# raspi_mockup.net
KiCad netlist of a schematic drawn in EAGLE
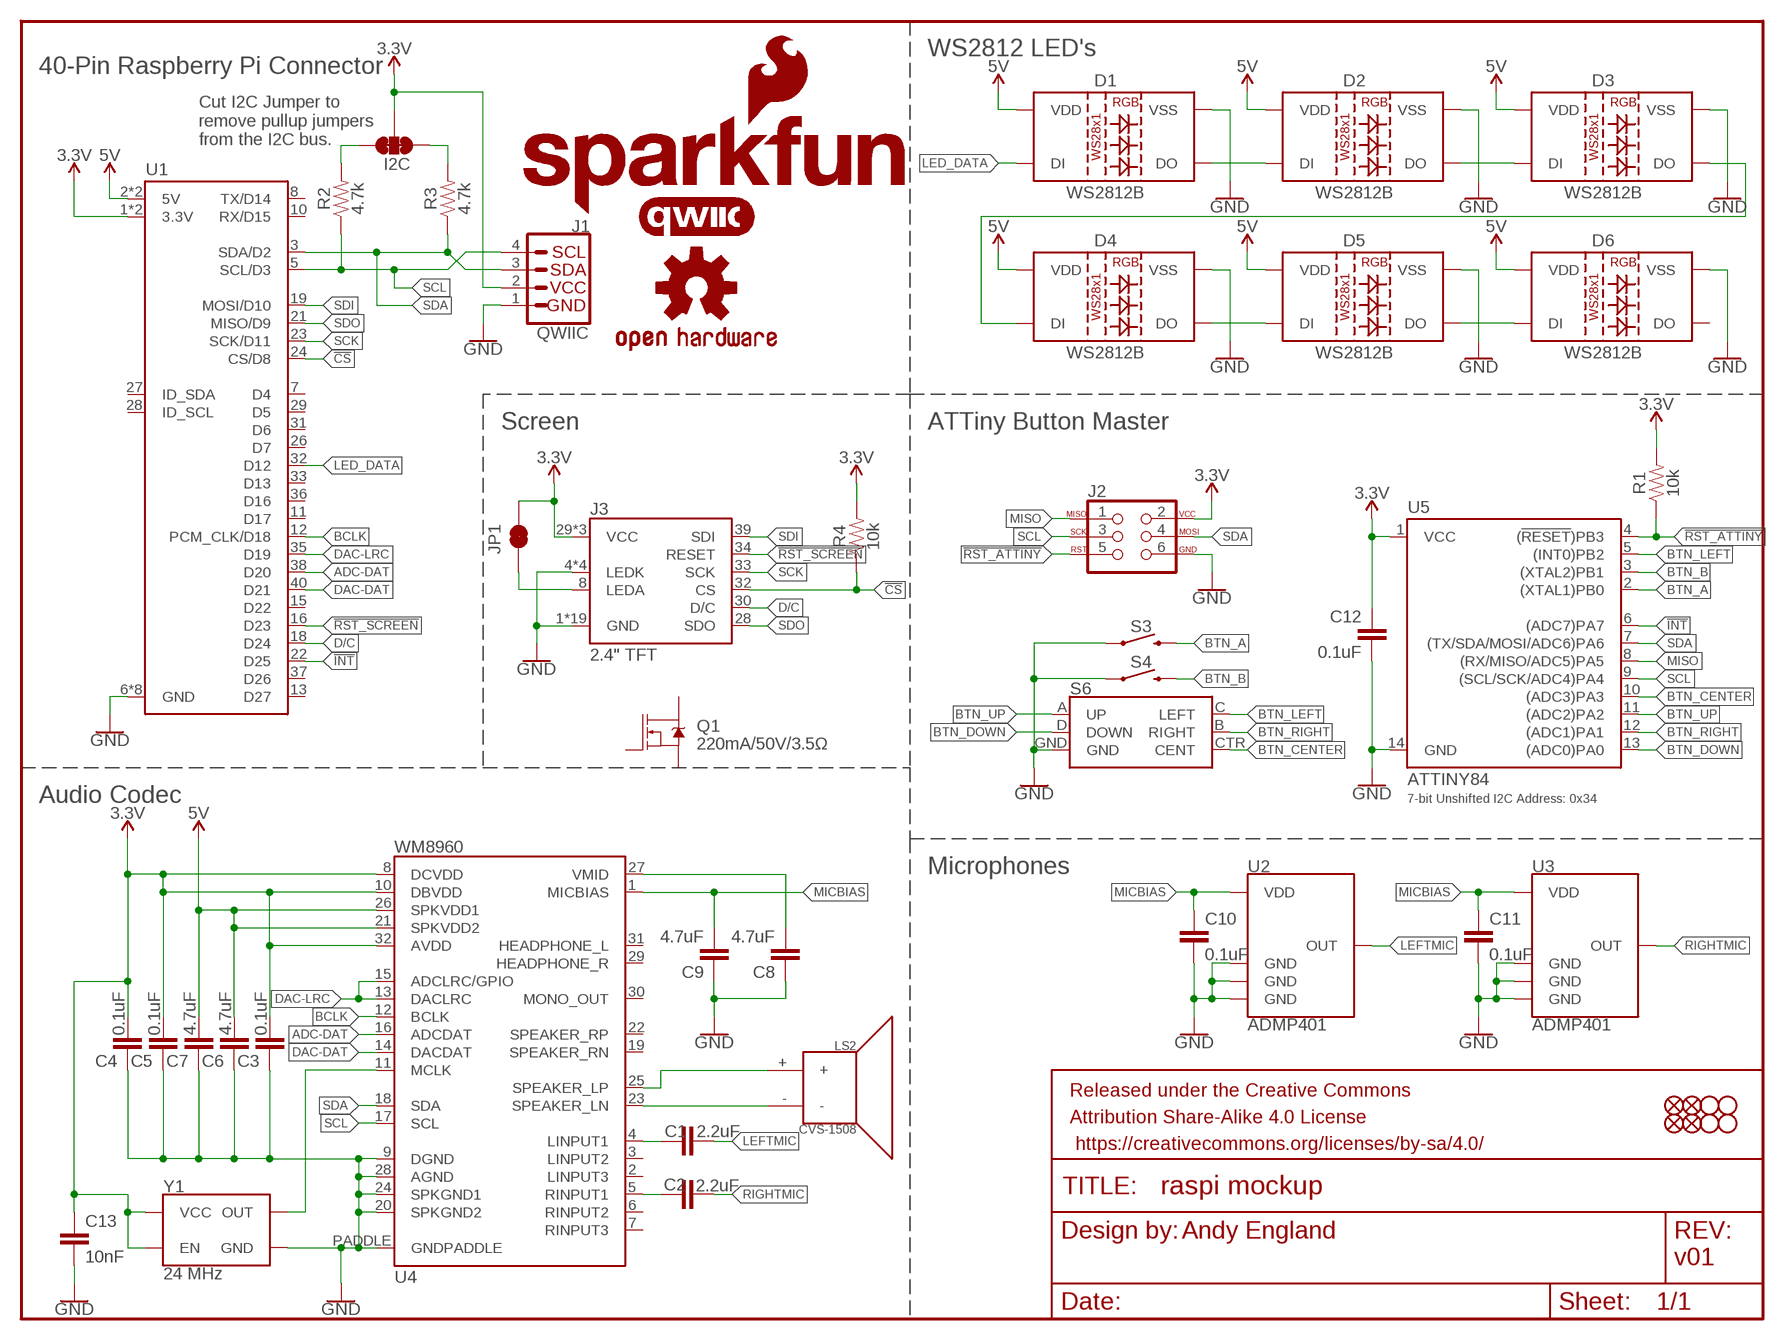
[diagram p0: schematic, sheet 1]

(export (version "E")
  (design (tool "Eeschema 10.0.6"))
  (components
    (comp (ref "C1")
      (value "2.2uF")
      (footprint "eagle-import:0603")
      (libsource (lib "eagle-import") (part "2.2UF-0603-10V-20%"))
    )
    (comp (ref "C2")
      (value "2.2uF")
      (footprint "eagle-import:0603")
      (libsource (lib "eagle-import") (part "2.2UF-0603-10V-20%"))
    )
    (comp (ref "C3")
      (value "0.1uF")
      (footprint "eagle-import:0603")
      (libsource (lib "eagle-import") (part "0.1UF-0603-25V-(+80/-20%)"))
    )
    (comp (ref "C4")
      (value "0.1uF")
      (footprint "eagle-import:0603")
      (libsource (lib "eagle-import") (part "0.1UF-0603-25V-(+80/-20%)"))
    )
    (comp (ref "C5")
      (value "0.1uF")
      (footprint "eagle-import:0603")
      (libsource (lib "eagle-import") (part "0.1UF-0603-25V-(+80/-20%)"))
    )
    (comp (ref "C6")
      (value "4.7uF")
      (footprint "eagle-import:0603")
      (libsource (lib "eagle-import") (part "4.7UF-0603-6.3V-(10%)"))
    )
    (comp (ref "C7")
      (value "4.7uF")
      (footprint "eagle-import:0603")
      (libsource (lib "eagle-import") (part "4.7UF-0603-6.3V-(10%)"))
    )
    (comp (ref "C8")
      (value "4.7uF")
      (footprint "eagle-import:0603")
      (libsource (lib "eagle-import") (part "4.7UF-0603-6.3V-(10%)"))
    )
    (comp (ref "C9")
      (value "4.7uF")
      (footprint "eagle-import:0603")
      (libsource (lib "eagle-import") (part "4.7UF-0603-6.3V-(10%)"))
    )
    (comp (ref "C10")
      (value "0.1uF")
      (footprint "eagle-import:0603")
      (libsource (lib "eagle-import") (part "0.1UF-0603-25V-(+80/-20%)"))
    )
    (comp (ref "C11")
      (value "0.1uF")
      (footprint "eagle-import:0603")
      (libsource (lib "eagle-import") (part "0.1UF-0603-25V-(+80/-20%)"))
    )
    (comp (ref "C12")
      (value "0.1uF")
      (footprint "eagle-import:0603")
      (libsource (lib "eagle-import") (part "0.1UF-0603-25V-(+80/-20%)"))
    )
    (comp (ref "C13")
      (value "10nF")
      (footprint "eagle-import:0603")
      (libsource (lib "eagle-import") (part "10NF-0603-50V-10%"))
    )
    (comp (ref "D1")
      (value "WS2812B")
      (footprint "eagle-import:WS2812B")
      (libsource (lib "eagle-import") (part "WS2812B"))
    )
    (comp (ref "D2")
      (value "WS2812B")
      (footprint "eagle-import:WS2812B")
      (libsource (lib "eagle-import") (part "WS2812B"))
    )
    (comp (ref "D3")
      (value "WS2812B")
      (footprint "eagle-import:WS2812B")
      (libsource (lib "eagle-import") (part "WS2812B"))
    )
    (comp (ref "D4")
      (value "WS2812B")
      (footprint "eagle-import:WS2812B")
      (libsource (lib "eagle-import") (part "WS2812B"))
    )
    (comp (ref "D5")
      (value "WS2812B")
      (footprint "eagle-import:WS2812B")
      (libsource (lib "eagle-import") (part "WS2812B"))
    )
    (comp (ref "D6")
      (value "WS2812B")
      (footprint "eagle-import:WS2812B")
      (libsource (lib "eagle-import") (part "WS2812B"))
    )
    (comp (ref "FD1")
      (value "FIDUCIAL1X2")
      (footprint "eagle-import:FIDUCIAL-1X2")
      (libsource (lib "eagle-import") (part "FIDUCIAL1X2"))
    )
    (comp (ref "FD2")
      (value "FIDUCIAL1X2")
      (footprint "eagle-import:FIDUCIAL-1X2")
      (libsource (lib "eagle-import") (part "FIDUCIAL1X2"))
    )
    (comp (ref "FD3")
      (value "FIDUCIAL1X2")
      (footprint "eagle-import:FIDUCIAL-1X2")
      (libsource (lib "eagle-import") (part "FIDUCIAL1X2"))
    )
    (comp (ref "FD4")
      (value "FIDUCIAL1X2")
      (footprint "eagle-import:FIDUCIAL-1X2")
      (libsource (lib "eagle-import") (part "FIDUCIAL1X2"))
    )
    (comp (ref "FRAME1")
      (value "FRAME-LETTER")
      (footprint "eagle-import:CREATIVE_COMMONS")
      (libsource (lib "eagle-import") (part "FRAME-LETTER"))
    )
    (comp (ref "H1")
      (value "STAND-OFFTIGHT")
      (footprint "eagle-import:STAND-OFF-TIGHT")
      (libsource (lib "eagle-import") (part "STAND-OFFTIGHT"))
    )
    (comp (ref "H2")
      (value "STAND-OFFTIGHT")
      (footprint "eagle-import:STAND-OFF-TIGHT")
      (libsource (lib "eagle-import") (part "STAND-OFFTIGHT"))
    )
    (comp (ref "H3")
      (value "STAND-OFFTIGHT")
      (footprint "eagle-import:STAND-OFF-TIGHT")
      (libsource (lib "eagle-import") (part "STAND-OFFTIGHT"))
    )
    (comp (ref "H4")
      (value "STAND-OFFTIGHT")
      (footprint "eagle-import:STAND-OFF-TIGHT")
      (libsource (lib "eagle-import") (part "STAND-OFFTIGHT"))
    )
    (comp (ref "I2C")
      (value "JUMPER-SMT_3_2-NC_TRACE_NO-SILK")
      (footprint "eagle-import:SMT-JUMPER_3_2-NC_TRACE_NO-SILK")
      (libsource (lib "eagle-import") (part "JUMPER-SMT_3_2-NC_TRACE_NO-SILK"))
    )
    (comp (ref "J1")
      (value "QWIIC")
      (footprint "eagle-import:JST04_1MM_RA")
      (libsource (lib "eagle-import") (part "QWIIC_CONNECTORJS-1MM"))
    )
    (comp (ref "J2")
      (value "AVR_SPI_PROG_3X2TESTPOINTS")
      (footprint "eagle-import:2X3_TEST_POINTS")
      (libsource (lib "eagle-import") (part "AVR_SPI_PROG_3X2TESTPOINTS"))
    )
    (comp (ref "J3")
      (value "2.4\" TFT")
      (footprint "eagle-import:FPC05040-17204")
      (libsource (lib "eagle-import") (part "4DLCD-24-320X240"))
    )
    (comp (ref "JP1")
      (value "JUMPER-SMT_2_NC_TRACE_NO-SILK")
      (footprint "eagle-import:SMT-JUMPER_2_NC_TRACE_NO-SILK")
      (libsource (lib "eagle-import") (part "JUMPER-SMT_2_NC_TRACE_NO-SILK"))
    )
    (comp (ref "LOGO1")
      (value "SFE_LOGO_NAME_FLAME.1_INCH")
      (footprint "eagle-import:SFE_LOGO_NAME_FLAME_.1")
      (libsource (lib "eagle-import") (part "SFE_LOGO_NAME_FLAME.1_INCH"))
    )
    (comp (ref "LOGO2")
      (value "SFE_LOGO_NAME_FLAME.4_INCH")
      (footprint "eagle-import:SFE_LOGO_NAME_FLAME_.4")
      (libsource (lib "eagle-import") (part "SFE_LOGO_NAME_FLAME.4_INCH"))
    )
    (comp (ref "LOGO3")
      (value "QWIIC_LOGO_4MM")
      (footprint "eagle-import:QWIIC_4MM")
      (libsource (lib "eagle-import") (part "QWIIC_LOGO_4MM"))
    )
    (comp (ref "LOGO4")
      (value "OSHW-LOGOS")
      (footprint "eagle-import:OSHW-LOGO-S")
      (libsource (lib "eagle-import") (part "OSHW-LOGOS"))
    )
    (comp (ref "LS2")
      (value "CVS-1508")
      (footprint "eagle-import:CVS-1508_PCBSPKR")
      (libsource (lib "eagle-import") (part "SPEAKERCVS-1508"))
    )
    (comp (ref "Q1")
      (value "220mA/50V/3.5Ω")
      (footprint "eagle-import:SOT23-3")
      (libsource (lib "eagle-import") (part "MOSFET-NCH-BSS138"))
    )
    (comp (ref "R1")
      (value "10k")
      (footprint "eagle-import:0603")
      (libsource (lib "eagle-import") (part "10KOHM-0603-1/10W-1%"))
    )
    (comp (ref "R2")
      (value "4.7k")
      (footprint "eagle-import:0603")
      (libsource (lib "eagle-import") (part "4.7KOHM-0603-1/10W-1%"))
    )
    (comp (ref "R3")
      (value "4.7k")
      (footprint "eagle-import:0603")
      (libsource (lib "eagle-import") (part "4.7KOHM-0603-1/10W-1%"))
    )
    (comp (ref "R4")
      (value "10k")
      (footprint "eagle-import:0603")
      (libsource (lib "eagle-import") (part "10KOHM-0603-1/10W-1%"))
    )
    (comp (ref "S3")
      (value "MOMENTARY-SWITCH-SPST-SMD-5.2MM-TALL")
      (footprint "eagle-import:TACTILE_SWITCH_SMD_5.2MM")
      (libsource (lib "eagle-import") (part "MOMENTARY-SWITCH-SPST-SMD-5.2MM-TALL"))
    )
    (comp (ref "S4")
      (value "MOMENTARY-SWITCH-SPST-SMD-5.2MM-TALL")
      (footprint "eagle-import:TACTILE_SWITCH_SMD_5.2MM")
      (libsource (lib "eagle-import") (part "MOMENTARY-SWITCH-SPST-SMD-5.2MM-TALL"))
    )
    (comp (ref "S6")
      (value "JOYSTICK_MINI")
      (footprint "eagle-import:JOYSTICK_MINI")
      (libsource (lib "eagle-import") (part "JOYSTICK_MINI"))
    )
    (comp (ref "U1")
      (value "RASPBERRY_PI_40BTM-NOHOLES")
      (footprint "eagle-import:RASPBERRY_PI_SHIELD_BOTTOM_ENTRY_NOHOLES")
      (libsource (lib "eagle-import") (part "RASPBERRY_PI_40BTM-NOHOLES"))
    )
    (comp (ref "U2")
      (value "ADMP401")
      (footprint "eagle-import:ADMP401")
      (libsource (lib "eagle-import") (part "ADMP401"))
    )
    (comp (ref "U3")
      (value "ADMP401")
      (footprint "eagle-import:ADMP401")
      (libsource (lib "eagle-import") (part "ADMP401"))
    )
    (comp (ref "U4")
      (value "WM8960")
      (footprint "eagle-import:QFN-32")
      (libsource (lib "eagle-import") (part "WM8960"))
    )
    (comp (ref "U5")
      (value "ATTINY84")
      (footprint "eagle-import:SO14")
      (libsource (lib "eagle-import") (part "ATTINY84"))
    )
    (comp (ref "Y1")
      (value "24 MHz")
      (footprint "eagle-import:RESONATOR-SMD-3.2X2.5")
      (libsource (lib "eagle-import") (part "OSCILLATOR-24MHZ"))
    )
  )
  (nets
    (net (code "1") (name "/~{CS}") (class "Default")
      (node (ref "J3") (pin "32") (pinfunction "CS_32") (pintype "bidirectional"))
      (node (ref "R4") (pin "1") (pinfunction "1_1") (pintype "passive"))
      (node (ref "U1") (pin "24") (pinfunction "CS/D8_24") (pintype "bidirectional"))
    )
    (net (code "2") (name "/~{INT}") (class "Default")
      (node (ref "U1") (pin "22") (pinfunction "D25_22") (pintype "bidirectional"))
      (node (ref "U5") (pin "6") (pinfunction "(ADC7)PA7_6") (pintype "bidirectional"))
    )
    (net (code "3") (name "/~{RST_ATTINY}") (class "Default")
      (node (ref "J2") (pin "5") (pinfunction "5_5") (pintype "passive"))
      (node (ref "R1") (pin "1") (pinfunction "1_1") (pintype "passive"))
      (node (ref "U5") (pin "4") (pinfunction "(~{RESET})PB3_4") (pintype "bidirectional"))
    )
    (net (code "4") (name "/~{RST_SCREEN}") (class "Default")
      (node (ref "J3") (pin "34") (pinfunction "RESET_34") (pintype "bidirectional"))
      (node (ref "U1") (pin "16") (pinfunction "D23_16") (pintype "bidirectional"))
    )
    (net (code "5") (name "3.3V") (class "Default")
      (node (ref "C12") (pin "1") (pinfunction "1_1") (pintype "passive"))
      (node (ref "C13") (pin "1") (pinfunction "1_1") (pintype "passive"))
      (node (ref "C3") (pin "2") (pinfunction "2_2") (pintype "passive"))
      (node (ref "C4") (pin "2") (pinfunction "2_2") (pintype "passive"))
      (node (ref "C5") (pin "2") (pinfunction "2_2") (pintype "passive"))
      (node (ref "I2C") (pin "2") (pinfunction "2_2") (pintype "passive"))
      (node (ref "J1") (pin "2") (pinfunction "2_2") (pintype "power_in"))
      (node (ref "J2") (pin "2") (pinfunction "2_2") (pintype "passive"))
      (node (ref "J3") (pin "29") (pinfunction "VCC_29") (pintype "bidirectional"))
      (node (ref "J3") (pin "31") (pinfunction "VCC_31") (pintype "bidirectional"))
      (node (ref "J3") (pin "38") (pinfunction "VCC_38") (pintype "bidirectional"))
      (node (ref "JP1") (pin "2") (pinfunction "2_2") (pintype "passive"))
      (node (ref "R1") (pin "2") (pinfunction "2_2") (pintype "passive"))
      (node (ref "R4") (pin "2") (pinfunction "2_2") (pintype "passive"))
      (node (ref "U1") (pin "1") (pinfunction "3.3V_1") (pintype "bidirectional"))
      (node (ref "U1") (pin "17") (pinfunction "3.3V_17") (pintype "bidirectional"))
      (node (ref "U4") (pin "10") (pinfunction "DBVDD_10") (pintype "bidirectional"))
      (node (ref "U4") (pin "32") (pinfunction "AVDD_32") (pintype "bidirectional"))
      (node (ref "U4") (pin "8") (pinfunction "DCVDD_8") (pintype "bidirectional"))
      (node (ref "U5") (pin "1") (pinfunction "VCC_1") (pintype "bidirectional"))
      (node (ref "Y1") (pin "1") (pinfunction "EN_1") (pintype "bidirectional"))
      (node (ref "Y1") (pin "4") (pinfunction "VCC_4") (pintype "bidirectional"))
    )
    (net (code "6") (name "5V") (class "Default")
      (node (ref "C6") (pin "2") (pinfunction "2_2") (pintype "passive"))
      (node (ref "C7") (pin "2") (pinfunction "2_2") (pintype "passive"))
      (node (ref "D1") (pin "1") (pinfunction "VDD_1") (pintype "bidirectional"))
      (node (ref "D2") (pin "1") (pinfunction "VDD_1") (pintype "bidirectional"))
      (node (ref "D3") (pin "1") (pinfunction "VDD_1") (pintype "bidirectional"))
      (node (ref "D4") (pin "1") (pinfunction "VDD_1") (pintype "bidirectional"))
      (node (ref "D5") (pin "1") (pinfunction "VDD_1") (pintype "bidirectional"))
      (node (ref "D6") (pin "1") (pinfunction "VDD_1") (pintype "bidirectional"))
      (node (ref "U1") (pin "2") (pinfunction "5V_2") (pintype "bidirectional"))
      (node (ref "U1") (pin "4") (pinfunction "5V_4") (pintype "bidirectional"))
      (node (ref "U4") (pin "21") (pinfunction "SPKVDD2_21") (pintype "bidirectional"))
      (node (ref "U4") (pin "26") (pinfunction "SPKVDD1_26") (pintype "bidirectional"))
    )
    (net (code "7") (name "ADC-DAT") (class "Default")
      (node (ref "U1") (pin "38") (pinfunction "D20_38") (pintype "bidirectional"))
      (node (ref "U4") (pin "16") (pinfunction "ADCDAT_16") (pintype "bidirectional"))
    )
    (net (code "8") (name "BCLK") (class "Default")
      (node (ref "U1") (pin "12") (pinfunction "PCM_CLK/D18_12") (pintype "bidirectional"))
      (node (ref "U4") (pin "12") (pinfunction "BCLK_12") (pintype "bidirectional"))
    )
    (net (code "9") (name "BTN_A") (class "Default")
      (node (ref "S3") (pin "3") (pinfunction "2_3") (pintype "passive"))
      (node (ref "U5") (pin "2") (pinfunction "(XTAL1)PB0_2") (pintype "bidirectional"))
    )
    (net (code "10") (name "BTN_B") (class "Default")
      (node (ref "S4") (pin "3") (pinfunction "2_3") (pintype "passive"))
      (node (ref "U5") (pin "3") (pinfunction "(XTAL2)PB1_3") (pintype "bidirectional"))
    )
    (net (code "11") (name "BTN_CENTER") (class "Default")
      (node (ref "S6") (pin "CTR") (pinfunction "CENT_CTR") (pintype "bidirectional"))
      (node (ref "U5") (pin "10") (pinfunction "(ADC3)PA3_10") (pintype "bidirectional"))
    )
    (net (code "12") (name "BTN_DOWN") (class "Default")
      (node (ref "S6") (pin "D") (pinfunction "DOWN_D") (pintype "bidirectional"))
      (node (ref "U5") (pin "13") (pinfunction "(ADC0)PA0_13") (pintype "bidirectional"))
    )
    (net (code "13") (name "BTN_LEFT") (class "Default")
      (node (ref "S6") (pin "C") (pinfunction "LEFT_C") (pintype "bidirectional"))
      (node (ref "U5") (pin "5") (pinfunction "(INT0)PB2_5") (pintype "bidirectional"))
    )
    (net (code "14") (name "BTN_RIGHT") (class "Default")
      (node (ref "S6") (pin "B") (pinfunction "RIGHT_B") (pintype "bidirectional"))
      (node (ref "U5") (pin "12") (pinfunction "(ADC1)PA1_12") (pintype "bidirectional"))
    )
    (net (code "15") (name "BTN_UP") (class "Default")
      (node (ref "S6") (pin "A") (pinfunction "UP_A") (pintype "bidirectional"))
      (node (ref "U5") (pin "11") (pinfunction "(ADC2)PA2_11") (pintype "bidirectional"))
    )
    (net (code "16") (name "DAC-DAT") (class "Default")
      (node (ref "U1") (pin "40") (pinfunction "D21_40") (pintype "bidirectional"))
      (node (ref "U4") (pin "14") (pinfunction "DACDAT_14") (pintype "bidirectional"))
    )
    (net (code "17") (name "DAC-LRC") (class "Default")
      (node (ref "U1") (pin "35") (pinfunction "D19_35") (pintype "bidirectional"))
      (node (ref "U4") (pin "13") (pinfunction "DACLRC_13") (pintype "bidirectional"))
      (node (ref "U4") (pin "15") (pinfunction "ADCLRC/GPIO_15") (pintype "bidirectional"))
    )
    (net (code "18") (name "D{slash}C") (class "Default")
      (node (ref "J3") (pin "30") (pinfunction "D/C_30") (pintype "bidirectional"))
      (node (ref "U1") (pin "18") (pinfunction "D24_18") (pintype "bidirectional"))
    )
    (net (code "19") (name "GND") (class "Default")
      (node (ref "C10") (pin "2") (pinfunction "2_2") (pintype "passive"))
      (node (ref "C11") (pin "2") (pinfunction "2_2") (pintype "passive"))
      (node (ref "C12") (pin "2") (pinfunction "2_2") (pintype "passive"))
      (node (ref "C13") (pin "2") (pinfunction "2_2") (pintype "passive"))
      (node (ref "C3") (pin "1") (pinfunction "1_1") (pintype "passive"))
      (node (ref "C4") (pin "1") (pinfunction "1_1") (pintype "passive"))
      (node (ref "C5") (pin "1") (pinfunction "1_1") (pintype "passive"))
      (node (ref "C6") (pin "1") (pinfunction "1_1") (pintype "passive"))
      (node (ref "C7") (pin "1") (pinfunction "1_1") (pintype "passive"))
      (node (ref "C8") (pin "1") (pinfunction "1_1") (pintype "passive"))
      (node (ref "C9") (pin "1") (pinfunction "1_1") (pintype "passive"))
      (node (ref "D1") (pin "3") (pinfunction "VSS_3") (pintype "bidirectional"))
      (node (ref "D2") (pin "3") (pinfunction "VSS_3") (pintype "bidirectional"))
      (node (ref "D3") (pin "3") (pinfunction "VSS_3") (pintype "bidirectional"))
      (node (ref "D4") (pin "3") (pinfunction "VSS_3") (pintype "bidirectional"))
      (node (ref "D5") (pin "3") (pinfunction "VSS_3") (pintype "bidirectional"))
      (node (ref "D6") (pin "3") (pinfunction "VSS_3") (pintype "bidirectional"))
      (node (ref "J1") (pin "1") (pinfunction "1_1") (pintype "power_in"))
      (node (ref "J2") (pin "6") (pinfunction "6_6") (pintype "passive"))
      (node (ref "J3") (pin "1") (pinfunction "GND_1") (pintype "bidirectional"))
      (node (ref "J3") (pin "11") (pinfunction "GND_11") (pintype "bidirectional"))
      (node (ref "J3") (pin "12") (pinfunction "GND_12") (pintype "bidirectional"))
      (node (ref "J3") (pin "13") (pinfunction "GND_13") (pintype "bidirectional"))
      (node (ref "J3") (pin "14") (pinfunction "GND_14") (pintype "bidirectional"))
      (node (ref "J3") (pin "15") (pinfunction "GND_15") (pintype "bidirectional"))
      (node (ref "J3") (pin "16") (pinfunction "GND_16") (pintype "bidirectional"))
      (node (ref "J3") (pin "17") (pinfunction "GND_17") (pintype "bidirectional"))
      (node (ref "J3") (pin "18") (pinfunction "GND_18") (pintype "bidirectional"))
      (node (ref "J3") (pin "19") (pinfunction "GND_19") (pintype "bidirectional"))
      (node (ref "J3") (pin "20") (pinfunction "GND_20") (pintype "bidirectional"))
      (node (ref "J3") (pin "21") (pinfunction "GND_21") (pintype "bidirectional"))
      (node (ref "J3") (pin "22") (pinfunction "GND_22") (pintype "bidirectional"))
      (node (ref "J3") (pin "23") (pinfunction "GND_23") (pintype "bidirectional"))
      (node (ref "J3") (pin "24") (pinfunction "GND_24") (pintype "bidirectional"))
      (node (ref "J3") (pin "25") (pinfunction "GND_25") (pintype "bidirectional"))
      (node (ref "J3") (pin "26") (pinfunction "GND_26") (pintype "bidirectional"))
      (node (ref "J3") (pin "27") (pinfunction "GND_27") (pintype "bidirectional"))
      (node (ref "J3") (pin "4") (pinfunction "LEDK_4") (pintype "bidirectional"))
      (node (ref "J3") (pin "40") (pinfunction "GND_40") (pintype "bidirectional"))
      (node (ref "J3") (pin "5") (pinfunction "LEDK_5") (pintype "bidirectional"))
      (node (ref "J3") (pin "6") (pinfunction "LEDK_6") (pintype "bidirectional"))
      (node (ref "J3") (pin "7") (pinfunction "LEDK_7") (pintype "bidirectional"))
      (node (ref "S3") (pin "1") (pinfunction "1_1") (pintype "passive"))
      (node (ref "S4") (pin "1") (pinfunction "1_1") (pintype "passive"))
      (node (ref "S6") (pin "GND") (pinfunction "GND_GND") (pintype "bidirectional"))
      (node (ref "U1") (pin "14") (pinfunction "GND_14") (pintype "bidirectional"))
      (node (ref "U1") (pin "20") (pinfunction "GND_20") (pintype "bidirectional"))
      (node (ref "U1") (pin "25") (pinfunction "GND_25") (pintype "bidirectional"))
      (node (ref "U1") (pin "30") (pinfunction "GND_30") (pintype "bidirectional"))
      (node (ref "U1") (pin "34") (pinfunction "GND_34") (pintype "bidirectional"))
      (node (ref "U1") (pin "39") (pinfunction "GND_39") (pintype "bidirectional"))
      (node (ref "U1") (pin "6") (pinfunction "GND_6") (pintype "bidirectional"))
      (node (ref "U1") (pin "9") (pinfunction "GND_9") (pintype "bidirectional"))
      (node (ref "U2") (pin "2") (pinfunction "GND_2") (pintype "bidirectional"))
      (node (ref "U2") (pin "4") (pinfunction "GND_4") (pintype "bidirectional"))
      (node (ref "U2") (pin "6") (pinfunction "GND_6") (pintype "bidirectional"))
      (node (ref "U3") (pin "2") (pinfunction "GND_2") (pintype "bidirectional"))
      (node (ref "U3") (pin "4") (pinfunction "GND_4") (pintype "bidirectional"))
      (node (ref "U3") (pin "6") (pinfunction "GND_6") (pintype "bidirectional"))
      (node (ref "U4") (pin "20") (pinfunction "SPKGND2_20") (pintype "bidirectional"))
      (node (ref "U4") (pin "24") (pinfunction "SPKGND1_24") (pintype "bidirectional"))
      (node (ref "U4") (pin "28") (pinfunction "AGND_28") (pintype "bidirectional"))
      (node (ref "U4") (pin "9") (pinfunction "DGND_9") (pintype "bidirectional"))
      (node (ref "U4") (pin "PADDLE") (pinfunction "GNDPADDLE_PADDLE") (pintype "bidirectional"))
      (node (ref "U5") (pin "14") (pinfunction "GND_14") (pintype "bidirectional"))
      (node (ref "Y1") (pin "2") (pinfunction "GND_2") (pintype "bidirectional"))
    )
    (net (code "20") (name "LED_DATA") (class "Default")
      (node (ref "D1") (pin "4") (pinfunction "DI_4") (pintype "bidirectional"))
      (node (ref "U1") (pin "32") (pinfunction "D12_32") (pintype "bidirectional"))
    )
    (net (code "21") (name "LEFTMIC") (class "Default")
      (node (ref "C1") (pin "2") (pinfunction "2_2") (pintype "passive"))
      (node (ref "U2") (pin "1") (pinfunction "OUT_1") (pintype "bidirectional"))
    )
    (net (code "22") (name "MICBIAS") (class "Default")
      (node (ref "C10") (pin "1") (pinfunction "1_1") (pintype "passive"))
      (node (ref "C11") (pin "1") (pinfunction "1_1") (pintype "passive"))
      (node (ref "C9") (pin "2") (pinfunction "2_2") (pintype "passive"))
      (node (ref "U2") (pin "5") (pinfunction "VDD_5") (pintype "bidirectional"))
      (node (ref "U3") (pin "5") (pinfunction "VDD_5") (pintype "bidirectional"))
      (node (ref "U4") (pin "1") (pinfunction "MICBIAS_1") (pintype "bidirectional"))
    )
    (net (code "23") (name "MISO") (class "Default")
      (node (ref "J2") (pin "1") (pinfunction "1_1") (pintype "passive"))
      (node (ref "U5") (pin "8") (pinfunction "(RX/MISO/ADC5)PA5_8") (pintype "bidirectional"))
    )
    (net (code "24") (name "Net-(D1-DO)") (class "Default")
      (node (ref "D1") (pin "2") (pinfunction "DO_2") (pintype "bidirectional"))
      (node (ref "D2") (pin "4") (pinfunction "DI_4") (pintype "bidirectional"))
    )
    (net (code "25") (name "Net-(D2-DO)") (class "Default")
      (node (ref "D2") (pin "2") (pinfunction "DO_2") (pintype "bidirectional"))
      (node (ref "D3") (pin "4") (pinfunction "DI_4") (pintype "bidirectional"))
    )
    (net (code "26") (name "Net-(D3-DO)") (class "Default")
      (node (ref "D3") (pin "2") (pinfunction "DO_2") (pintype "bidirectional"))
      (node (ref "D4") (pin "4") (pinfunction "DI_4") (pintype "bidirectional"))
    )
    (net (code "27") (name "Net-(D4-DO)") (class "Default")
      (node (ref "D4") (pin "2") (pinfunction "DO_2") (pintype "bidirectional"))
      (node (ref "D5") (pin "4") (pinfunction "DI_4") (pintype "bidirectional"))
    )
    (net (code "28") (name "Net-(D5-DO)") (class "Default")
      (node (ref "D5") (pin "2") (pinfunction "DO_2") (pintype "bidirectional"))
      (node (ref "D6") (pin "4") (pinfunction "DI_4") (pintype "bidirectional"))
    )
    (net (code "29") (name "Net-(I2C-Pad1)") (class "Default")
      (node (ref "I2C") (pin "1") (pinfunction "1_1") (pintype "passive"))
      (node (ref "R3") (pin "2") (pinfunction "2_2") (pintype "passive"))
    )
    (net (code "30") (name "Net-(I2C-Pad3)") (class "Default")
      (node (ref "I2C") (pin "3") (pinfunction "3_3") (pintype "passive"))
      (node (ref "R2") (pin "2") (pinfunction "2_2") (pintype "passive"))
    )
    (net (code "31") (name "Net-(J3-LEDA)") (class "Default")
      (node (ref "J3") (pin "8") (pinfunction "LEDA_8") (pintype "bidirectional"))
      (node (ref "JP1") (pin "1") (pinfunction "1_1") (pintype "passive"))
    )
    (net (code "32") (name "Net-(U4-LINPUT1)") (class "Default")
      (node (ref "C1") (pin "1") (pinfunction "1_1") (pintype "passive"))
      (node (ref "U4") (pin "4") (pinfunction "LINPUT1_4") (pintype "bidirectional"))
    )
    (net (code "33") (name "Net-(U4-MCLK)") (class "Default")
      (node (ref "U4") (pin "11") (pinfunction "MCLK_11") (pintype "bidirectional"))
      (node (ref "Y1") (pin "3") (pinfunction "OUT_3") (pintype "bidirectional"))
    )
    (net (code "34") (name "Net-(U4-RINPUT1)") (class "Default")
      (node (ref "C2") (pin "1") (pinfunction "1_1") (pintype "passive"))
      (node (ref "U4") (pin "5") (pinfunction "RINPUT1_5") (pintype "bidirectional"))
    )
    (net (code "35") (name "Net-(U4-SPEAKER_LN)") (class "Default")
      (node (ref "LS2") (pin "-") (pinfunction "-_-") (pintype "bidirectional"))
      (node (ref "U4") (pin "23") (pinfunction "SPEAKER_LN_23") (pintype "bidirectional"))
    )
    (net (code "36") (name "Net-(U4-SPEAKER_LP)") (class "Default")
      (node (ref "LS2") (pin "+") (pinfunction "+_+") (pintype "bidirectional"))
      (node (ref "U4") (pin "25") (pinfunction "SPEAKER_LP_25") (pintype "bidirectional"))
    )
    (net (code "37") (name "Net-(U4-VMID)") (class "Default")
      (node (ref "C8") (pin "2") (pinfunction "2_2") (pintype "passive"))
      (node (ref "U4") (pin "27") (pinfunction "VMID_27") (pintype "bidirectional"))
    )
    (net (code "38") (name "RIGHTMIC") (class "Default")
      (node (ref "C2") (pin "2") (pinfunction "2_2") (pintype "passive"))
      (node (ref "U3") (pin "1") (pinfunction "OUT_1") (pintype "bidirectional"))
    )
    (net (code "39") (name "SCK") (class "Default")
      (node (ref "J3") (pin "33") (pinfunction "SCK_33") (pintype "bidirectional"))
      (node (ref "U1") (pin "23") (pinfunction "SCK/D11_23") (pintype "bidirectional"))
    )
    (net (code "40") (name "SCL") (class "Default")
      (node (ref "J1") (pin "4") (pinfunction "4_4") (pintype "passive"))
      (node (ref "J2") (pin "3") (pinfunction "3_3") (pintype "passive"))
      (node (ref "R2") (pin "1") (pinfunction "1_1") (pintype "passive"))
      (node (ref "U1") (pin "5") (pinfunction "SCL/D3_5") (pintype "bidirectional"))
      (node (ref "U4") (pin "17") (pinfunction "SCL_17") (pintype "bidirectional"))
      (node (ref "U5") (pin "9") (pinfunction "(SCL/SCK/ADC4)PA4_9") (pintype "bidirectional"))
    )
    (net (code "41") (name "SDA") (class "Default")
      (node (ref "J1") (pin "3") (pinfunction "3_3") (pintype "passive"))
      (node (ref "J2") (pin "4") (pinfunction "4_4") (pintype "passive"))
      (node (ref "R3") (pin "1") (pinfunction "1_1") (pintype "passive"))
      (node (ref "U1") (pin "3") (pinfunction "SDA/D2_3") (pintype "bidirectional"))
      (node (ref "U4") (pin "18") (pinfunction "SDA_18") (pintype "bidirectional"))
      (node (ref "U5") (pin "7") (pinfunction "(TX/SDA/MOSI/ADC6)PA6_7") (pintype "bidirectional"))
    )
    (net (code "42") (name "SDI") (class "Default")
      (node (ref "J3") (pin "39") (pinfunction "SDI_39") (pintype "bidirectional"))
      (node (ref "U1") (pin "19") (pinfunction "MOSI/D10_19") (pintype "bidirectional"))
    )
    (net (code "43") (name "SDO") (class "Default")
      (node (ref "J3") (pin "28") (pinfunction "SDO_28") (pintype "bidirectional"))
      (node (ref "U1") (pin "21") (pinfunction "MISO/D9_21") (pintype "bidirectional"))
    )
    (net (code "44") (name "unconnected-(D6-DO-Pad2)") (class "Default")
      (node (ref "D6") (pin "2") (pinfunction "DO_2") (pintype "bidirectional"))
    )
    (net (code "45") (name "unconnected-(Q1-D-Pad3)") (class "Default")
      (node (ref "Q1") (pin "3") (pinfunction "D_3") (pintype "bidirectional"))
    )
    (net (code "46") (name "unconnected-(Q1-G-Pad1)") (class "Default")
      (node (ref "Q1") (pin "1") (pinfunction "G_1") (pintype "bidirectional"))
    )
    (net (code "47") (name "unconnected-(Q1-S-Pad2)") (class "Default")
      (node (ref "Q1") (pin "2") (pinfunction "S_2") (pintype "bidirectional"))
    )
    (net (code "48") (name "unconnected-(U1-D4-Pad7)") (class "Default")
      (node (ref "U1") (pin "7") (pinfunction "D4_7") (pintype "bidirectional"))
    )
    (net (code "49") (name "unconnected-(U1-D5-Pad29)") (class "Default")
      (node (ref "U1") (pin "29") (pinfunction "D5_29") (pintype "bidirectional"))
    )
    (net (code "50") (name "unconnected-(U1-D6-Pad31)") (class "Default")
      (node (ref "U1") (pin "31") (pinfunction "D6_31") (pintype "bidirectional"))
    )
    (net (code "51") (name "unconnected-(U1-D7-Pad26)") (class "Default")
      (node (ref "U1") (pin "26") (pinfunction "D7_26") (pintype "bidirectional"))
    )
    (net (code "52") (name "unconnected-(U1-D13-Pad33)") (class "Default")
      (node (ref "U1") (pin "33") (pinfunction "D13_33") (pintype "bidirectional"))
    )
    (net (code "53") (name "unconnected-(U1-D16-Pad36)") (class "Default")
      (node (ref "U1") (pin "36") (pinfunction "D16_36") (pintype "bidirectional"))
    )
    (net (code "54") (name "unconnected-(U1-D17-Pad11)") (class "Default")
      (node (ref "U1") (pin "11") (pinfunction "D17_11") (pintype "bidirectional"))
    )
    (net (code "55") (name "unconnected-(U1-D22-Pad15)") (class "Default")
      (node (ref "U1") (pin "15") (pinfunction "D22_15") (pintype "bidirectional"))
    )
    (net (code "56") (name "unconnected-(U1-D26-Pad37)") (class "Default")
      (node (ref "U1") (pin "37") (pinfunction "D26_37") (pintype "bidirectional"))
    )
    (net (code "57") (name "unconnected-(U1-D27-Pad13)") (class "Default")
      (node (ref "U1") (pin "13") (pinfunction "D27_13") (pintype "bidirectional"))
    )
    (net (code "58") (name "unconnected-(U1-ID_SCL-Pad28)") (class "Default")
      (node (ref "U1") (pin "28") (pinfunction "ID_SCL_28") (pintype "bidirectional"))
    )
    (net (code "59") (name "unconnected-(U1-ID_SDA-Pad27)") (class "Default")
      (node (ref "U1") (pin "27") (pinfunction "ID_SDA_27") (pintype "bidirectional"))
    )
    (net (code "60") (name "unconnected-(U1-RX{slash}D15-Pad10)") (class "Default")
      (node (ref "U1") (pin "10") (pinfunction "RX/D15_10") (pintype "bidirectional"))
    )
    (net (code "61") (name "unconnected-(U1-TX{slash}D14-Pad8)") (class "Default")
      (node (ref "U1") (pin "8") (pinfunction "TX/D14_8") (pintype "bidirectional"))
    )
    (net (code "62") (name "unconnected-(U4-HEADPHONE_L-Pad31)") (class "Default")
      (node (ref "U4") (pin "31") (pinfunction "HEADPHONE_L_31") (pintype "bidirectional"))
    )
    (net (code "63") (name "unconnected-(U4-HEADPHONE_R-Pad29)") (class "Default")
      (node (ref "U4") (pin "29") (pinfunction "HEADPHONE_R_29") (pintype "bidirectional"))
    )
    (net (code "64") (name "unconnected-(U4-LINPUT2-Pad3)") (class "Default")
      (node (ref "U4") (pin "3") (pinfunction "LINPUT2_3") (pintype "bidirectional"))
    )
    (net (code "65") (name "unconnected-(U4-LINPUT3-Pad2)") (class "Default")
      (node (ref "U4") (pin "2") (pinfunction "LINPUT3_2") (pintype "bidirectional"))
    )
    (net (code "66") (name "unconnected-(U4-MONO_OUT-Pad30)") (class "Default")
      (node (ref "U4") (pin "30") (pinfunction "MONO_OUT_30") (pintype "bidirectional"))
    )
    (net (code "67") (name "unconnected-(U4-RINPUT2-Pad6)") (class "Default")
      (node (ref "U4") (pin "6") (pinfunction "RINPUT2_6") (pintype "bidirectional"))
    )
    (net (code "68") (name "unconnected-(U4-RINPUT3-Pad7)") (class "Default")
      (node (ref "U4") (pin "7") (pinfunction "RINPUT3_7") (pintype "bidirectional"))
    )
    (net (code "69") (name "unconnected-(U4-SPEAKER_RN-Pad19)") (class "Default")
      (node (ref "U4") (pin "19") (pinfunction "SPEAKER_RN_19") (pintype "bidirectional"))
    )
    (net (code "70") (name "unconnected-(U4-SPEAKER_RP-Pad22)") (class "Default")
      (node (ref "U4") (pin "22") (pinfunction "SPEAKER_RP_22") (pintype "bidirectional"))
    )
  )
)
